# res15_nrf905_v2.net
KiCad netlist of a schematic drawn in EAGLE
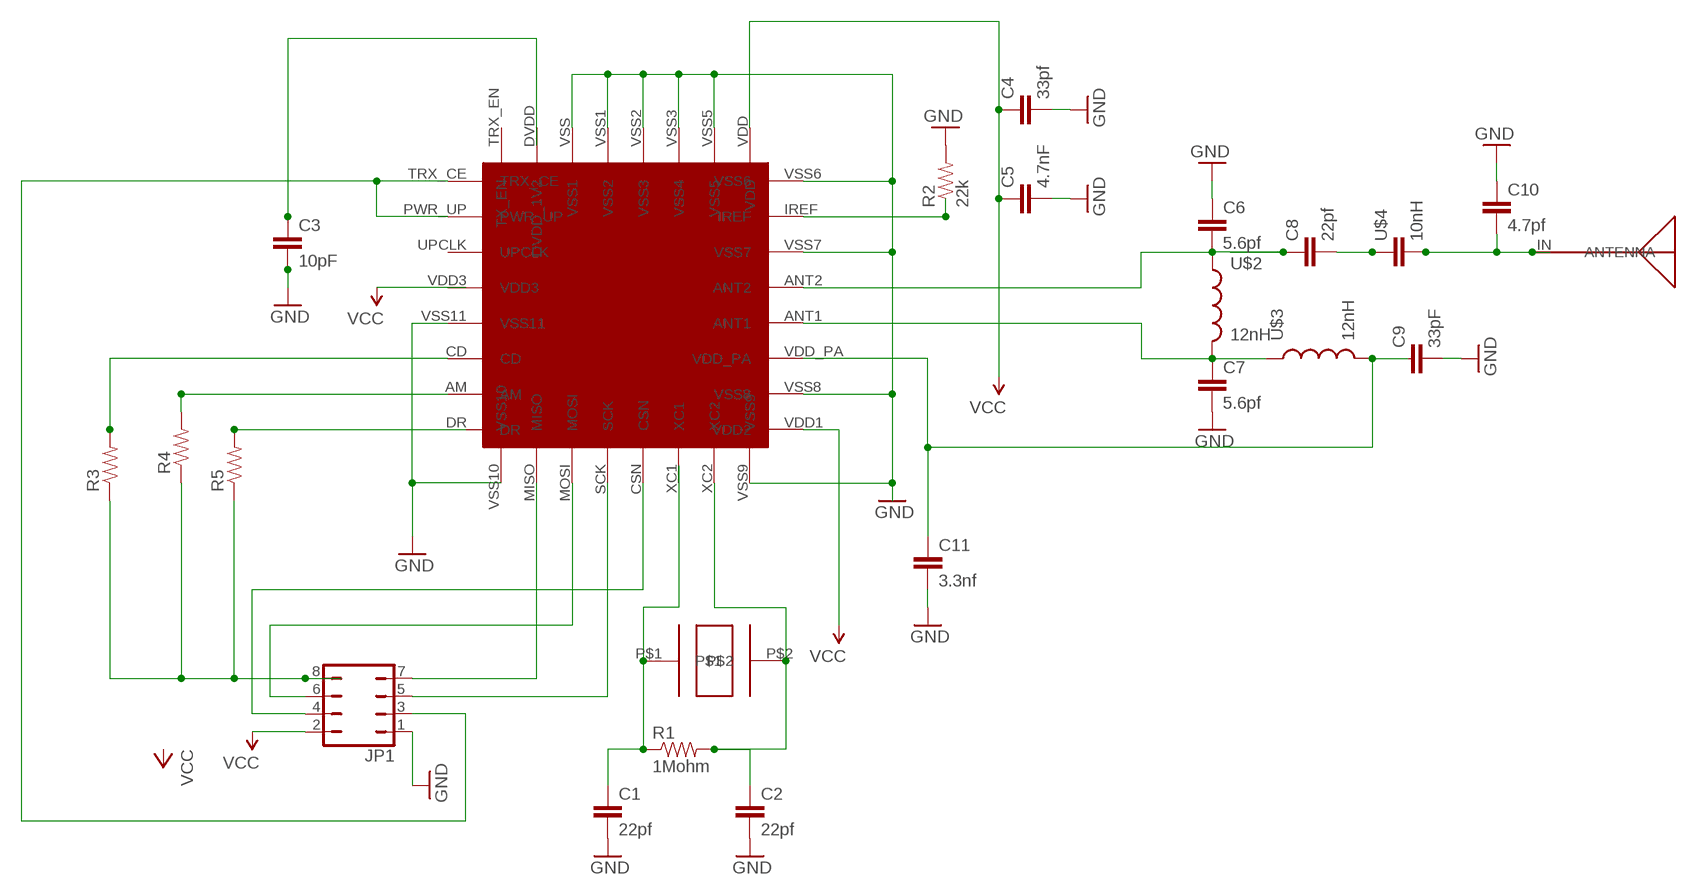
[diagram p0: schematic, sheet 1]

(export (version "E")
  (design (tool "Eeschema 10.0.6"))
  (components
    (comp (ref "C1")
      (value "22pf")
      (footprint "eagle-import:0603-CAP")
      (libsource (lib "eagle-import") (part "CAP0603-CAP"))
    )
    (comp (ref "C2")
      (value "22pf")
      (footprint "eagle-import:0603-CAP")
      (libsource (lib "eagle-import") (part "CAP0603-CAP"))
    )
    (comp (ref "C3")
      (value "10pF")
      (footprint "eagle-import:0603-CAP")
      (libsource (lib "eagle-import") (part "CAP0603-CAP"))
    )
    (comp (ref "C4")
      (value "33pf")
      (footprint "eagle-import:0603-CAP")
      (libsource (lib "eagle-import") (part "CAP0603-CAP"))
    )
    (comp (ref "C5")
      (value "4.7nF")
      (footprint "eagle-import:0603-CAP")
      (libsource (lib "eagle-import") (part "CAP0603-CAP"))
    )
    (comp (ref "C6")
      (value "5.6pf")
      (footprint "eagle-import:0603-CAP")
      (libsource (lib "eagle-import") (part "CAP0603-CAP"))
    )
    (comp (ref "C7")
      (value "5.6pf")
      (footprint "eagle-import:0603-CAP")
      (libsource (lib "eagle-import") (part "CAP0603-CAP"))
    )
    (comp (ref "C8")
      (value "22pf")
      (footprint "eagle-import:0603-CAP")
      (libsource (lib "eagle-import") (part "CAP0603-CAP"))
    )
    (comp (ref "C9")
      (value "33pF")
      (footprint "eagle-import:0603-CAP")
      (libsource (lib "eagle-import") (part "CAP0603-CAP"))
    )
    (comp (ref "C10")
      (value "4.7pf")
      (footprint "eagle-import:0603-CAP")
      (libsource (lib "eagle-import") (part "CAP0603-CAP"))
    )
    (comp (ref "C11")
      (value "3.3nf")
      (footprint "eagle-import:0603-CAP")
      (libsource (lib "eagle-import") (part "CAP0603-CAP"))
    )
    (comp (ref "JP1")
      (value "JP4Q")
      (footprint "eagle-import:JP4Q")
      (libsource (lib "eagle-import") (part "JP4Q"))
    )
    (comp (ref "R1")
      (value "1Mohm")
      (footprint "eagle-import:0603-RES")
      (libsource (lib "eagle-import") (part "RESISTOR0603-RES"))
    )
    (comp (ref "R2")
      (value "22k")
      (footprint "eagle-import:0603-RES")
      (libsource (lib "eagle-import") (part "RESISTOR0603-RES"))
    )
    (comp (ref "R3")
      (value "RESISTOR0603-RES")
      (footprint "eagle-import:0603-RES")
      (libsource (lib "eagle-import") (part "RESISTOR0603-RES"))
    )
    (comp (ref "R4")
      (value "RESISTOR0603-RES")
      (footprint "eagle-import:0603-RES")
      (libsource (lib "eagle-import") (part "RESISTOR0603-RES"))
    )
    (comp (ref "R5")
      (value "RESISTOR0603-RES")
      (footprint "eagle-import:0603-RES")
      (libsource (lib "eagle-import") (part "RESISTOR0603-RES"))
    )
    (comp (ref "U$1")
      (value "NRF905")
      (footprint "eagle-import:NRF905")
      (libsource (lib "eagle-import") (part "NRF905"))
    )
    (comp (ref "U$2")
      (value "12nH")
      (footprint "eagle-import:0603")
      (libsource (lib "eagle-import") (part "INDUCTOR0603"))
    )
    (comp (ref "U$3")
      (value "12nH")
      (footprint "eagle-import:0603")
      (libsource (lib "eagle-import") (part "INDUCTOR0603"))
    )
    (comp (ref "U$4")
      (value "10nH")
      (footprint "eagle-import:0603-CAP")
      (libsource (lib "eagle-import") (part "CAP0603-CAP"))
    )
    (comp (ref "U$5")
      (value "WURTH-7488910092")
      (footprint "eagle-import:WURTH-7488910092")
      (libsource (lib "eagle-import") (part "WURTH-7488910092"))
    )
    (comp (ref "U$6")
      (value "HC46X")
      (footprint "eagle-import:HC46X")
      (libsource (lib "eagle-import") (part "HC46X"))
    )
  )
  (nets
    (net (code "1") (name "/DR") (class "Default")
      (node (ref "U$1") (pin "DR") (pinfunction "DR_DR") (pintype "power_in"))
    )
    (net (code "2") (name "/VDD3") (class "Default")
      (node (ref "U$1") (pin "VDD3") (pinfunction "VDD3_VDD3") (pintype "power_in"))
    )
    (net (code "3") (name "GND") (class "Default")
      (node (ref "C1") (pin "2") (pinfunction "2_2") (pintype "passive"))
      (node (ref "C10") (pin "1") (pinfunction "1_1") (pintype "passive"))
      (node (ref "C11") (pin "2") (pinfunction "2_2") (pintype "passive"))
      (node (ref "C2") (pin "2") (pinfunction "2_2") (pintype "passive"))
      (node (ref "C3") (pin "2") (pinfunction "2_2") (pintype "passive"))
      (node (ref "C4") (pin "2") (pinfunction "2_2") (pintype "passive"))
      (node (ref "C5") (pin "2") (pinfunction "2_2") (pintype "passive"))
      (node (ref "C6") (pin "1") (pinfunction "1_1") (pintype "passive"))
      (node (ref "C7") (pin "2") (pinfunction "2_2") (pintype "passive"))
      (node (ref "C9") (pin "2") (pinfunction "2_2") (pintype "passive"))
      (node (ref "JP1") (pin "1") (pinfunction "1_1") (pintype "passive"))
      (node (ref "R2") (pin "2") (pinfunction "2_2") (pintype "passive"))
      (node (ref "U$1") (pin "VSS") (pinfunction "VSS1_VSS") (pintype "power_in"))
      (node (ref "U$1") (pin "VSS1") (pinfunction "VSS2_VSS1") (pintype "power_in"))
      (node (ref "U$1") (pin "VSS10") (pinfunction "VSS10_VSS10") (pintype "bidirectional"))
      (node (ref "U$1") (pin "VSS11") (pinfunction "VSS11_VSS11") (pintype "power_in"))
      (node (ref "U$1") (pin "VSS2") (pinfunction "VSS3_VSS2") (pintype "power_in"))
      (node (ref "U$1") (pin "VSS3") (pinfunction "VSS4_VSS3") (pintype "bidirectional"))
      (node (ref "U$1") (pin "VSS5") (pinfunction "VSS5_VSS5") (pintype "power_in"))
      (node (ref "U$1") (pin "VSS6") (pinfunction "VSS6_VSS6") (pintype "power_in"))
      (node (ref "U$1") (pin "VSS7") (pinfunction "VSS7_VSS7") (pintype "power_in"))
      (node (ref "U$1") (pin "VSS8") (pinfunction "VSS8_VSS8") (pintype "power_in"))
      (node (ref "U$1") (pin "VSS9") (pinfunction "VSS9_VSS9") (pintype "power_in"))
    )
    (net (code "4") (name "Net-(C1-Pad1)") (class "Default")
      (node (ref "C1") (pin "1") (pinfunction "1_1") (pintype "passive"))
      (node (ref "R1") (pin "1") (pinfunction "1_1") (pintype "passive"))
      (node (ref "U$6") (pin "P$1") (pinfunction "P$1_P$1") (pintype "bidirectional"))
    )
    (net (code "5") (name "Net-(C2-Pad1)") (class "Default")
      (node (ref "C2") (pin "1") (pinfunction "1_1") (pintype "passive"))
      (node (ref "R1") (pin "2") (pinfunction "2_2") (pintype "passive"))
      (node (ref "U$1") (pin "XC2") (pinfunction "XC2_XC2") (pintype "input"))
      (node (ref "U$6") (pin "P$2") (pinfunction "P$2_P$2") (pintype "bidirectional"))
    )
    (net (code "6") (name "Net-(C6-Pad2)") (class "Default")
      (node (ref "C6") (pin "2") (pinfunction "2_2") (pintype "passive"))
      (node (ref "C8") (pin "1") (pinfunction "1_1") (pintype "passive"))
      (node (ref "U$1") (pin "ANT2") (pinfunction "ANT2_ANT2") (pintype "output"))
      (node (ref "U$2") (pin "1") (pinfunction "1_1") (pintype "passive"))
    )
    (net (code "7") (name "Net-(C7-Pad1)") (class "Default")
      (node (ref "C7") (pin "1") (pinfunction "1_1") (pintype "passive"))
      (node (ref "U$1") (pin "ANT1") (pinfunction "ANT1_ANT1") (pintype "output"))
      (node (ref "U$2") (pin "2") (pinfunction "2_2") (pintype "passive"))
      (node (ref "U$3") (pin "1") (pinfunction "1_1") (pintype "passive"))
    )
    (net (code "8") (name "Net-(C8-Pad2)") (class "Default")
      (node (ref "C8") (pin "2") (pinfunction "2_2") (pintype "passive"))
      (node (ref "U$4") (pin "1") (pinfunction "1_1") (pintype "passive"))
    )
    (net (code "9") (name "Net-(C11-Pad1)") (class "Default")
      (node (ref "C11") (pin "1") (pinfunction "1_1") (pintype "passive"))
      (node (ref "U$1") (pin "VDD_PA") (pinfunction "VDD_PA_VDD_PA") (pintype "output"))
      (node (ref "U$3") (pin "2") (pinfunction "2_2") (pintype "passive"))
    )
    (net (code "10") (name "Net-(JP1-Pad3)") (class "Default")
      (node (ref "JP1") (pin "3") (pinfunction "3_3") (pintype "passive"))
      (node (ref "U$1") (pin "PWR_UP") (pinfunction "PWR_UP_PWR_UP") (pintype "input"))
      (node (ref "U$1") (pin "TRX_CE") (pinfunction "TRX_CE_TRX_CE") (pintype "bidirectional"))
    )
    (net (code "11") (name "Net-(JP1-Pad4)") (class "Default")
      (node (ref "JP1") (pin "4") (pinfunction "4_4") (pintype "passive"))
      (node (ref "U$1") (pin "CSN") (pinfunction "CSN_CSN") (pintype "bidirectional"))
    )
    (net (code "12") (name "Net-(JP1-Pad5)") (class "Default")
      (node (ref "JP1") (pin "5") (pinfunction "5_5") (pintype "passive"))
      (node (ref "U$1") (pin "SCK") (pinfunction "SCK_SCK") (pintype "bidirectional"))
    )
    (net (code "13") (name "Net-(JP1-Pad6)") (class "Default")
      (node (ref "JP1") (pin "6") (pinfunction "6_6") (pintype "passive"))
      (node (ref "U$1") (pin "MOSI") (pinfunction "MOSI_MOSI") (pintype "bidirectional"))
    )
    (net (code "14") (name "Net-(JP1-Pad7)") (class "Default")
      (node (ref "JP1") (pin "7") (pinfunction "7_7") (pintype "passive"))
      (node (ref "U$1") (pin "MISO") (pinfunction "MISO_MISO") (pintype "bidirectional"))
    )
    (net (code "15") (name "Net-(JP1-Pad8)") (class "Default")
      (node (ref "JP1") (pin "8") (pinfunction "8_8") (pintype "passive"))
      (node (ref "R3") (pin "1") (pinfunction "1_1") (pintype "passive"))
      (node (ref "R4") (pin "1") (pinfunction "1_1") (pintype "passive"))
      (node (ref "R5") (pin "1") (pinfunction "1_1") (pintype "passive"))
    )
    (net (code "16") (name "Net-(R2-Pad1)") (class "Default")
      (node (ref "R2") (pin "1") (pinfunction "1_1") (pintype "passive"))
      (node (ref "U$1") (pin "IREF") (pinfunction "IREF_IREF") (pintype "bidirectional"))
    )
    (net (code "17") (name "Net-(R3-Pad2)") (class "Default")
      (node (ref "R3") (pin "2") (pinfunction "2_2") (pintype "passive"))
      (node (ref "U$1") (pin "CD") (pinfunction "CD_CD") (pintype "bidirectional"))
    )
    (net (code "18") (name "Net-(R4-Pad2)") (class "Default")
      (node (ref "R4") (pin "2") (pinfunction "2_2") (pintype "passive"))
      (node (ref "U$1") (pin "AM") (pinfunction "AM_AM") (pintype "bidirectional"))
    )
    (net (code "19") (name "Net-(U$5-ANTENNA)") (class "Default")
      (node (ref "C10") (pin "2") (pinfunction "2_2") (pintype "passive"))
      (node (ref "U$4") (pin "2") (pinfunction "2_2") (pintype "passive"))
      (node (ref "U$5") (pin "IN") (pinfunction "ANTENNA_IN") (pintype "input"))
    )
    (net (code "20") (name "VCC") (class "Default")
      (node (ref "C4") (pin "1") (pinfunction "1_1") (pintype "passive"))
      (node (ref "C5") (pin "1") (pinfunction "1_1") (pintype "passive"))
      (node (ref "JP1") (pin "2") (pinfunction "2_2") (pintype "passive"))
      (node (ref "U$1") (pin "VDD") (pinfunction "VDD_VDD") (pintype "power_in"))
      (node (ref "U$1") (pin "VDD1") (pinfunction "VDD2_VDD1") (pintype "power_in"))
    )
    (net (code "21") (name "unconnected-(C3-Pad1)") (class "Default")
      (node (ref "C3") (pin "1") (pinfunction "1_1") (pintype "passive"))
    )
    (net (code "22") (name "unconnected-(C9-Pad1)") (class "Default")
      (node (ref "C9") (pin "1") (pinfunction "1_1") (pintype "passive"))
    )
    (net (code "23") (name "unconnected-(R5-Pad2)") (class "Default")
      (node (ref "R5") (pin "2") (pinfunction "2_2") (pintype "passive"))
    )
    (net (code "24") (name "unconnected-(U$1-DVDD_1V2-PadDVDD)") (class "Default")
      (node (ref "U$1") (pin "DVDD") (pinfunction "DVDD_1V2_DVDD") (pintype "bidirectional"))
    )
    (net (code "25") (name "unconnected-(U$1-PadUPCLK)") (class "Default")
      (node (ref "U$1") (pin "UPCLK") (pinfunction "UPCLK_UPCLK") (pintype "input"))
    )
    (net (code "26") (name "unconnected-(U$1-PadXC1)") (class "Default")
      (node (ref "U$1") (pin "XC1") (pinfunction "XC1_XC1") (pintype "input"))
    )
    (net (code "27") (name "unconnected-(U$1-TX_EN-PadTRX_EN)") (class "Default")
      (node (ref "U$1") (pin "TRX_EN") (pinfunction "TX_EN_TRX_EN") (pintype "bidirectional"))
    )
  )
)
